# HV_Sense.net
KiCad netlist of a schematic drawn in Altium Designer
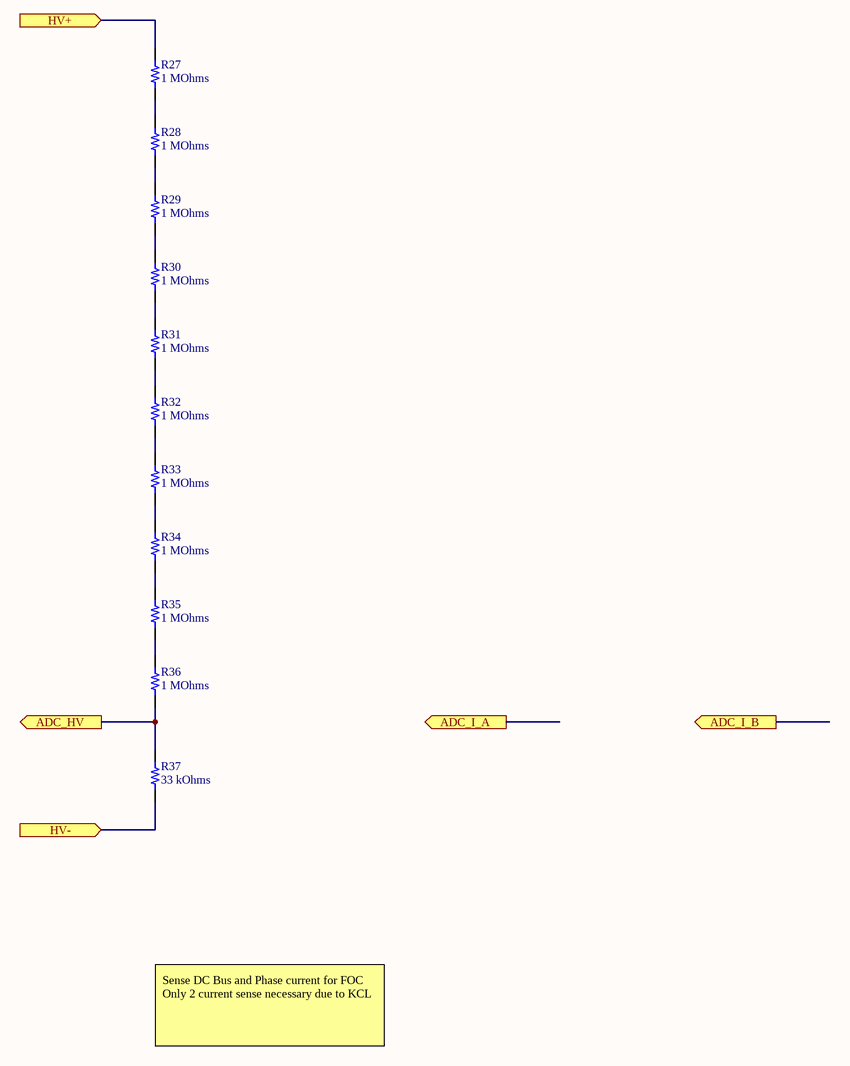
[diagram p0: HV Sense.SchDoc]

(export (version "E")
  (design (tool "Eeschema 10.0.6"))
  (components
    (comp (ref "R27")
      (value "1 MOhms")
      (footprint "RES 0805_2012")
      (description "RES 1M OHM 0.1% 1/8W 0805")
      (fields
        (field (name "PART NUMBER") "ERA-6AEB105V")
        (field (name "MANUFACTURER") "Panasonic Electronic Components")
      )
      (libsource (lib "Celestial Altium Library - altium_library") (part "Resistor"))
    )
    (comp (ref "R28")
      (value "1 MOhms")
      (footprint "RES 0805_2012")
      (description "RES 1M OHM 0.1% 1/8W 0805")
      (fields
        (field (name "PART NUMBER") "ERA-6AEB105V")
        (field (name "MANUFACTURER") "Panasonic Electronic Components")
      )
      (libsource (lib "Celestial Altium Library - altium_library") (part "Resistor"))
    )
    (comp (ref "R29")
      (value "1 MOhms")
      (footprint "RES 0805_2012")
      (description "RES 1M OHM 0.1% 1/8W 0805")
      (fields
        (field (name "PART NUMBER") "ERA-6AEB105V")
        (field (name "MANUFACTURER") "Panasonic Electronic Components")
      )
      (libsource (lib "Celestial Altium Library - altium_library") (part "Resistor"))
    )
    (comp (ref "R30")
      (value "1 MOhms")
      (footprint "RES 0805_2012")
      (description "RES 1M OHM 0.1% 1/8W 0805")
      (fields
        (field (name "PART NUMBER") "ERA-6AEB105V")
        (field (name "MANUFACTURER") "Panasonic Electronic Components")
      )
      (libsource (lib "Celestial Altium Library - altium_library") (part "Resistor"))
    )
    (comp (ref "R31")
      (value "1 MOhms")
      (footprint "RES 0805_2012")
      (description "RES 1M OHM 0.1% 1/8W 0805")
      (fields
        (field (name "PART NUMBER") "ERA-6AEB105V")
        (field (name "MANUFACTURER") "Panasonic Electronic Components")
      )
      (libsource (lib "Celestial Altium Library - altium_library") (part "Resistor"))
    )
    (comp (ref "R32")
      (value "1 MOhms")
      (footprint "RES 0805_2012")
      (description "RES 1M OHM 0.1% 1/8W 0805")
      (fields
        (field (name "PART NUMBER") "ERA-6AEB105V")
        (field (name "MANUFACTURER") "Panasonic Electronic Components")
      )
      (libsource (lib "Celestial Altium Library - altium_library") (part "Resistor"))
    )
    (comp (ref "R33")
      (value "1 MOhms")
      (footprint "RES 0805_2012")
      (description "RES 1M OHM 0.1% 1/8W 0805")
      (fields
        (field (name "PART NUMBER") "ERA-6AEB105V")
        (field (name "MANUFACTURER") "Panasonic Electronic Components")
      )
      (libsource (lib "Celestial Altium Library - altium_library") (part "Resistor"))
    )
    (comp (ref "R34")
      (value "1 MOhms")
      (footprint "RES 0805_2012")
      (description "RES 1M OHM 0.1% 1/8W 0805")
      (fields
        (field (name "PART NUMBER") "ERA-6AEB105V")
        (field (name "MANUFACTURER") "Panasonic Electronic Components")
      )
      (libsource (lib "Celestial Altium Library - altium_library") (part "Resistor"))
    )
    (comp (ref "R35")
      (value "1 MOhms")
      (footprint "RES 0805_2012")
      (description "RES 1M OHM 0.1% 1/8W 0805")
      (fields
        (field (name "PART NUMBER") "ERA-6AEB105V")
        (field (name "MANUFACTURER") "Panasonic Electronic Components")
      )
      (libsource (lib "Celestial Altium Library - altium_library") (part "Resistor"))
    )
    (comp (ref "R36")
      (value "1 MOhms")
      (footprint "RES 0805_2012")
      (description "RES 1M OHM 0.1% 1/8W 0805")
      (fields
        (field (name "PART NUMBER") "ERA-6AEB105V")
        (field (name "MANUFACTURER") "Panasonic Electronic Components")
      )
      (libsource (lib "Celestial Altium Library - altium_library") (part "Resistor"))
    )
    (comp (ref "R37")
      (value "33 kOhms")
      (footprint "RES 0805_2012")
      (description "RES 33K OHM 0.1% 1/8W 0805")
      (fields
        (field (name "PART NUMBER") "ERA-6ARB333V")
        (field (name "MANUFACTURER") "Panasonic Electronic Components")
      )
      (libsource (lib "Celestial Altium Library - altium_library") (part "Resistor"))
    )
  )
  (nets
    (net (code "1") (name "/ADC_HV") (class "Default")
      (node (ref "R36") (pin "1") (pinfunction "1_1") (pintype "passive"))
      (node (ref "R37") (pin "2") (pinfunction "2_2") (pintype "passive"))
    )
    (net (code "4") (name "/HV+") (class "Default")
      (node (ref "R27") (pin "2") (pinfunction "2_2") (pintype "passive"))
    )
    (net (code "5") (name "/HV-") (class "Default")
      (node (ref "R37") (pin "1") (pinfunction "1_1") (pintype "passive"))
    )
    (net (code "6") (name "Net-(R27-Pad1)") (class "Default")
      (node (ref "R27") (pin "1") (pinfunction "1_1") (pintype "passive"))
      (node (ref "R28") (pin "2") (pinfunction "2_2") (pintype "passive"))
    )
    (net (code "7") (name "Net-(R28-Pad1)") (class "Default")
      (node (ref "R28") (pin "1") (pinfunction "1_1") (pintype "passive"))
      (node (ref "R29") (pin "2") (pinfunction "2_2") (pintype "passive"))
    )
    (net (code "8") (name "Net-(R29-Pad1)") (class "Default")
      (node (ref "R29") (pin "1") (pinfunction "1_1") (pintype "passive"))
      (node (ref "R30") (pin "2") (pinfunction "2_2") (pintype "passive"))
    )
    (net (code "9") (name "Net-(R30-Pad1)") (class "Default")
      (node (ref "R30") (pin "1") (pinfunction "1_1") (pintype "passive"))
      (node (ref "R31") (pin "2") (pinfunction "2_2") (pintype "passive"))
    )
    (net (code "10") (name "Net-(R31-Pad1)") (class "Default")
      (node (ref "R31") (pin "1") (pinfunction "1_1") (pintype "passive"))
      (node (ref "R32") (pin "2") (pinfunction "2_2") (pintype "passive"))
    )
    (net (code "11") (name "Net-(R32-Pad1)") (class "Default")
      (node (ref "R32") (pin "1") (pinfunction "1_1") (pintype "passive"))
      (node (ref "R33") (pin "2") (pinfunction "2_2") (pintype "passive"))
    )
    (net (code "12") (name "Net-(R33-Pad1)") (class "Default")
      (node (ref "R33") (pin "1") (pinfunction "1_1") (pintype "passive"))
      (node (ref "R34") (pin "2") (pinfunction "2_2") (pintype "passive"))
    )
    (net (code "13") (name "Net-(R34-Pad1)") (class "Default")
      (node (ref "R34") (pin "1") (pinfunction "1_1") (pintype "passive"))
      (node (ref "R35") (pin "2") (pinfunction "2_2") (pintype "passive"))
    )
    (net (code "14") (name "Net-(R35-Pad1)") (class "Default")
      (node (ref "R35") (pin "1") (pinfunction "1_1") (pintype "passive"))
      (node (ref "R36") (pin "2") (pinfunction "2_2") (pintype "passive"))
    )
  )
)
